# DancingLightBluetoothSpeakerTE_MP_Projec.net
KiCad netlist of a schematic drawn in EAGLE
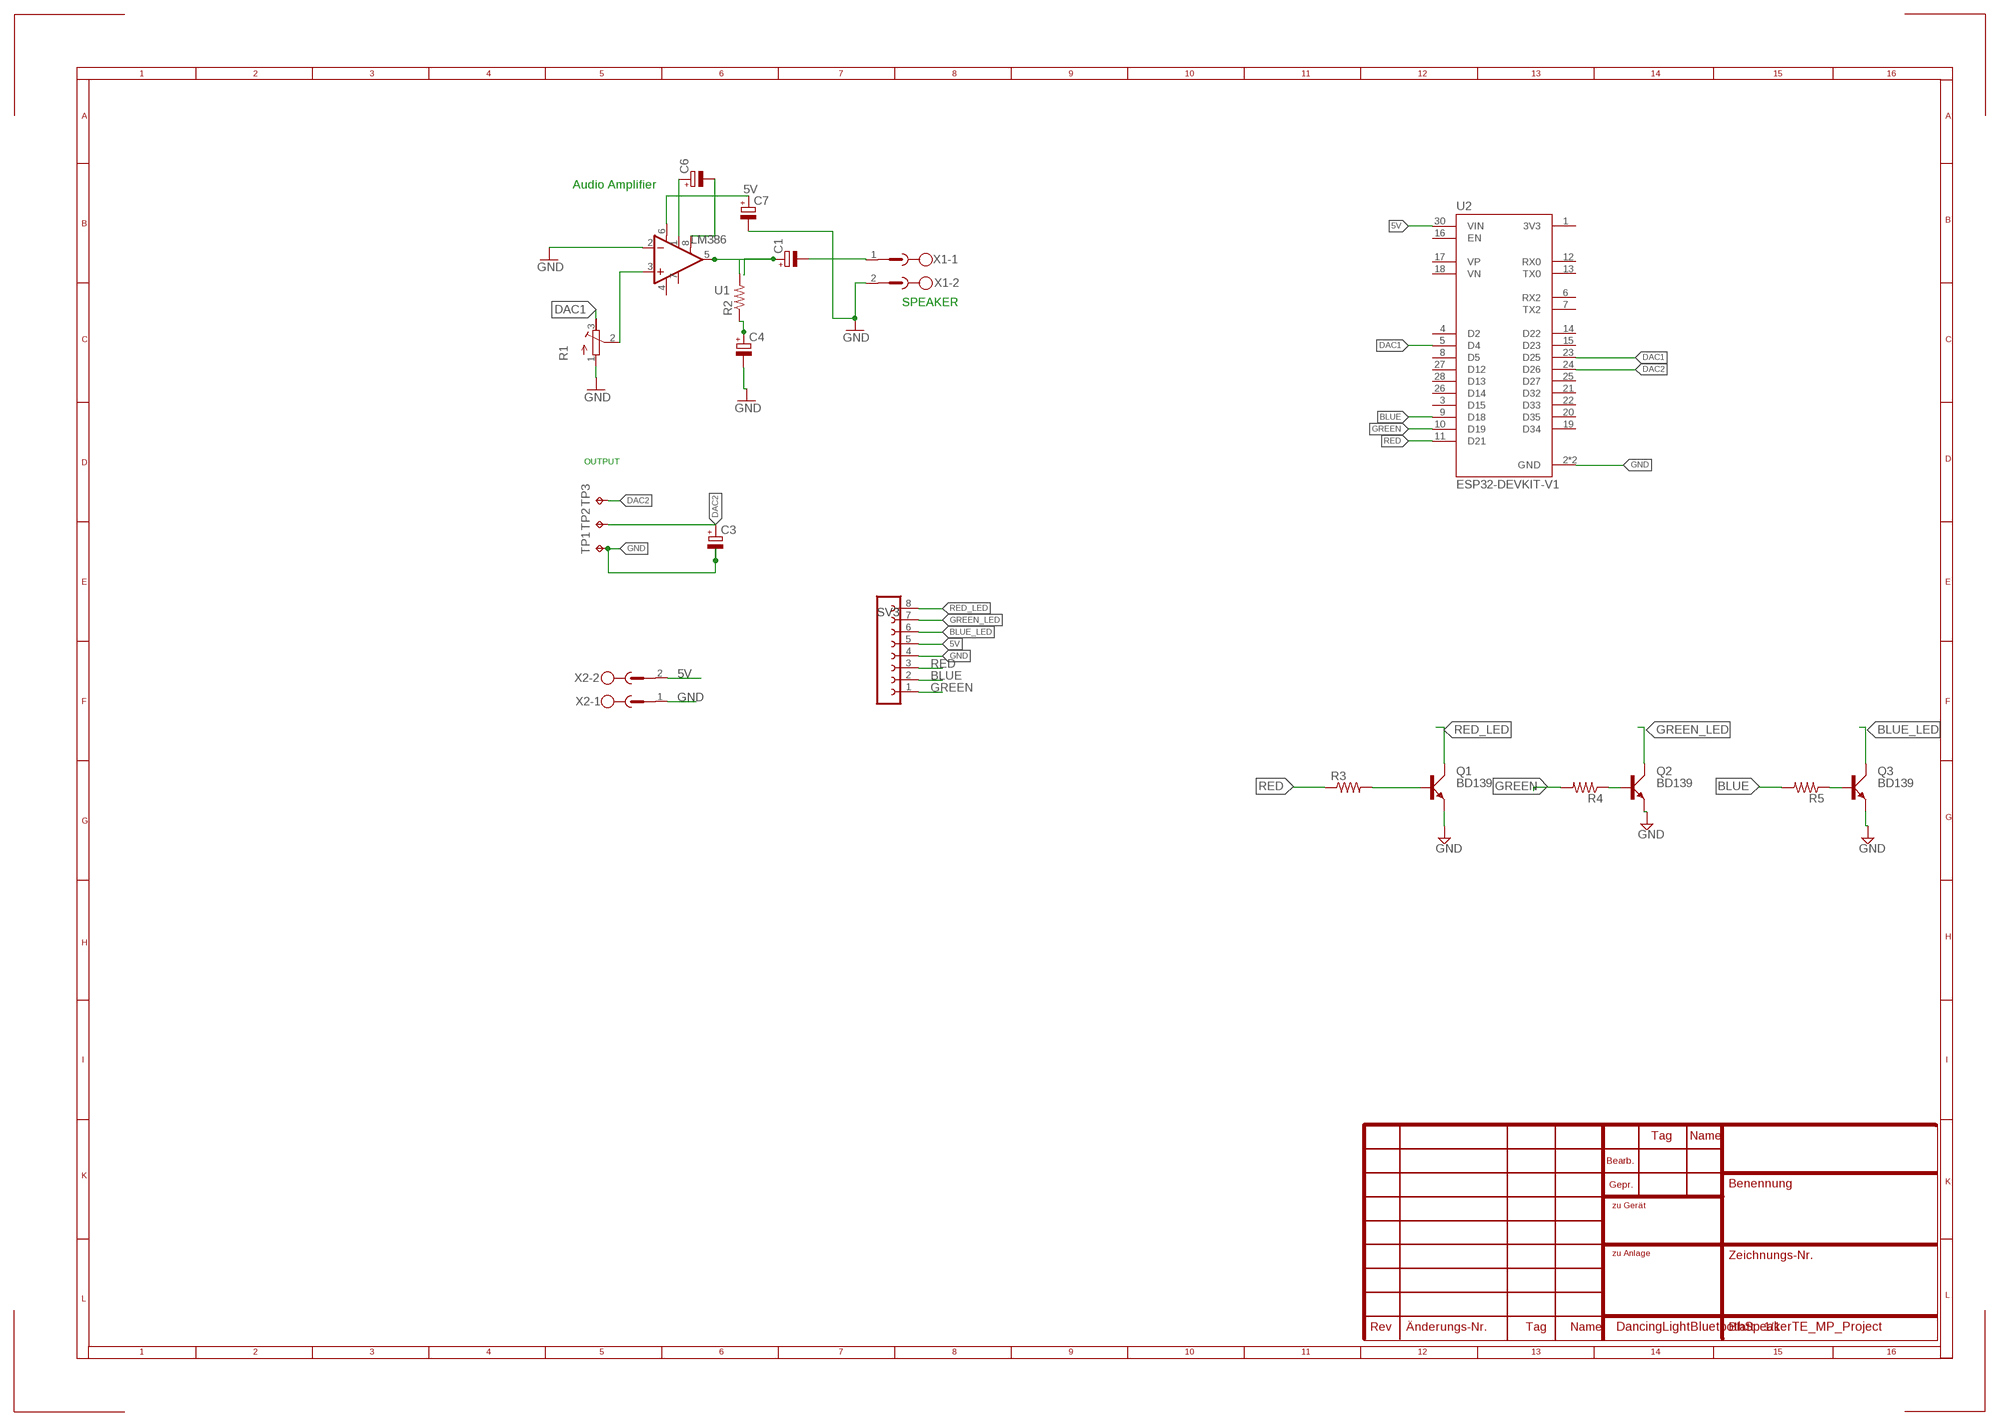
[diagram p0: schematic, sheet 1]

(export (version "E")
  (design (tool "Eeschema 10.0.6"))
  (components
    (comp (ref "C1")
      (value "CPOL-EUE2-5")
      (footprint "eagle-import:E2-5")
      (libsource (lib "eagle-import") (part "CPOL-EUE2-5"))
    )
    (comp (ref "C3")
      (value "CPOL-EUE2-5")
      (footprint "eagle-import:E2-5")
      (libsource (lib "eagle-import") (part "CPOL-EUE2-5"))
    )
    (comp (ref "C4")
      (value "CPOL-EUE2-5")
      (footprint "eagle-import:E2-5")
      (libsource (lib "eagle-import") (part "CPOL-EUE2-5"))
    )
    (comp (ref "C6")
      (value "CPOL-EUE2-5")
      (footprint "eagle-import:E2-5")
      (libsource (lib "eagle-import") (part "CPOL-EUE2-5"))
    )
    (comp (ref "C7")
      (value "CPOL-EUE2-5")
      (footprint "eagle-import:E2-5")
      (libsource (lib "eagle-import") (part "CPOL-EUE2-5"))
    )
    (comp (ref "Q1")
      (value "BD139")
      (footprint "eagle-import:TO126AV")
      (libsource (lib "eagle-import") (part "BD139"))
    )
    (comp (ref "Q2")
      (value "BD139")
      (footprint "eagle-import:TO126AV")
      (libsource (lib "eagle-import") (part "BD139"))
    )
    (comp (ref "Q3")
      (value "BD139")
      (footprint "eagle-import:TO126AV")
      (libsource (lib "eagle-import") (part "BD139"))
    )
    (comp (ref "R1")
      (value "R-TRIMM3339P")
      (footprint "eagle-import:RTRIM3339P")
      (libsource (lib "eagle-import") (part "R-TRIMM3339P"))
    )
    (comp (ref "R2")
      (value "R-US_0207/10")
      (footprint "eagle-import:0207_10")
      (libsource (lib "eagle-import") (part "R-US_0207/10"))
    )
    (comp (ref "R3")
      (value "R-US_0207/10")
      (footprint "eagle-import:0207_10")
      (libsource (lib "eagle-import") (part "R-US_0207/10"))
    )
    (comp (ref "R4")
      (value "R-US_0207/10")
      (footprint "eagle-import:0207_10")
      (libsource (lib "eagle-import") (part "R-US_0207/10"))
    )
    (comp (ref "R5")
      (value "R-US_0207/10")
      (footprint "eagle-import:0207_10")
      (libsource (lib "eagle-import") (part "R-US_0207/10"))
    )
    (comp (ref "SV3")
      (value "FE08-1")
      (footprint "eagle-import:FE08")
      (libsource (lib "eagle-import") (part "FE08-1"))
    )
    (comp (ref "TP1")
      (value "TPTP10SQ")
      (footprint "eagle-import:TP10SQ")
      (libsource (lib "eagle-import") (part "TPTP10SQ"))
    )
    (comp (ref "TP2")
      (value "TPTP10SQ")
      (footprint "eagle-import:TP10SQ")
      (libsource (lib "eagle-import") (part "TPTP10SQ"))
    )
    (comp (ref "TP3")
      (value "TPTP10SQ")
      (footprint "eagle-import:TP10SQ")
      (libsource (lib "eagle-import") (part "TPTP10SQ"))
    )
    (comp (ref "U1")
      (value "LM386")
      (footprint "eagle-import:DIP08")
      (fields (field (name "MF") "Texas Instruments"))
      (libsource (lib "eagle-import") (part "LM386"))
    )
    (comp (ref "U2")
      (value "ESP32-DEVKIT-V1")
      (footprint "eagle-import:MODULE_ESP32_DEVKIT_V1")
      (fields (field (name "MF") "Do it"))
      (libsource (lib "eagle-import") (part "ESP32-DEVKIT-V1"))
    )
    (comp (ref "X1")
      (value "MSTBV2")
      (footprint "eagle-import:MSTBV2")
      (libsource (lib "eagle-import") (part "MSTBV2"))
    )
    (comp (ref "X2")
      (value "MSTBV2")
      (footprint "eagle-import:MSTBV2")
      (libsource (lib "eagle-import") (part "MSTBV2"))
    )
  )
  (nets
    (net (code "1") (name "/V-") (class "Default")
      (node (ref "U1") (pin "4") (pinfunction "V-_4") (pintype "power_in"))
    )
    (net (code "2") (name "5V") (class "Default")
      (node (ref "C7") (pin "+") (pinfunction "+_+") (pintype "passive"))
      (node (ref "SV3") (pin "5") (pinfunction "5_5") (pintype "passive"))
      (node (ref "U1") (pin "6") (pinfunction "V+_6") (pintype "power_in"))
      (node (ref "U2") (pin "30") (pinfunction "VIN_30") (pintype "input"))
      (node (ref "X2") (pin "2") (pinfunction "SK_2") (pintype "passive"))
    )
    (net (code "3") (name "BLUE") (class "Default")
      (node (ref "R5") (pin "2") (pinfunction "2_2") (pintype "passive"))
      (node (ref "SV3") (pin "2") (pinfunction "2_2") (pintype "passive"))
      (node (ref "U2") (pin "9") (pinfunction "D18_9") (pintype "bidirectional"))
    )
    (net (code "4") (name "BLUE_LED") (class "Default")
      (node (ref "Q3") (pin "C") (pinfunction "C_C") (pintype "passive"))
      (node (ref "SV3") (pin "6") (pinfunction "6_6") (pintype "passive"))
    )
    (net (code "5") (name "DAC1") (class "Default")
      (node (ref "R1") (pin "3") (pinfunction "E_3") (pintype "passive"))
      (node (ref "U2") (pin "23") (pinfunction "D25_23") (pintype "bidirectional"))
      (node (ref "U2") (pin "5") (pinfunction "D4_5") (pintype "bidirectional"))
    )
    (net (code "6") (name "DAC2") (class "Default")
      (node (ref "C3") (pin "+") (pinfunction "+_+") (pintype "passive"))
      (node (ref "TP2") (pin "TP") (pinfunction "TP_TP") (pintype "input"))
      (node (ref "TP3") (pin "TP") (pinfunction "TP_TP") (pintype "input"))
      (node (ref "U2") (pin "24") (pinfunction "D26_24") (pintype "bidirectional"))
    )
    (net (code "7") (name "GND") (class "Default")
      (node (ref "C3") (pin "-") (pinfunction "-_-") (pintype "passive"))
      (node (ref "C4") (pin "-") (pinfunction "-_-") (pintype "passive"))
      (node (ref "C7") (pin "-") (pinfunction "-_-") (pintype "passive"))
      (node (ref "Q1") (pin "E") (pinfunction "E_E") (pintype "passive"))
      (node (ref "Q2") (pin "E") (pinfunction "E_E") (pintype "passive"))
      (node (ref "Q3") (pin "E") (pinfunction "E_E") (pintype "passive"))
      (node (ref "R1") (pin "1") (pinfunction "A_1") (pintype "passive"))
      (node (ref "SV3") (pin "4") (pinfunction "4_4") (pintype "passive"))
      (node (ref "TP1") (pin "TP") (pinfunction "TP_TP") (pintype "input"))
      (node (ref "U1") (pin "2") (pinfunction "-IN_2") (pintype "input"))
      (node (ref "U2") (pin "2") (pinfunction "GND_2") (pintype "power_in"))
      (node (ref "U2") (pin "29") (pinfunction "GND_29") (pintype "power_in"))
      (node (ref "X1") (pin "2") (pinfunction "SK_2") (pintype "passive"))
      (node (ref "X2") (pin "1") (pinfunction "SK_1") (pintype "passive"))
    )
    (net (code "8") (name "GREEN") (class "Default")
      (node (ref "R4") (pin "2") (pinfunction "2_2") (pintype "passive"))
      (node (ref "SV3") (pin "1") (pinfunction "1_1") (pintype "passive"))
      (node (ref "U2") (pin "10") (pinfunction "D19_10") (pintype "bidirectional"))
    )
    (net (code "9") (name "GREEN_LED") (class "Default")
      (node (ref "Q2") (pin "C") (pinfunction "C_C") (pintype "passive"))
      (node (ref "SV3") (pin "7") (pinfunction "7_7") (pintype "passive"))
    )
    (net (code "10") (name "Net-(C4-Pad+)") (class "Default")
      (node (ref "C4") (pin "+") (pinfunction "+_+") (pintype "passive"))
      (node (ref "R2") (pin "1") (pinfunction "1_1") (pintype "passive"))
    )
    (net (code "11") (name "Net-(C6-Pad+)") (class "Default")
      (node (ref "C6") (pin "+") (pinfunction "+_+") (pintype "passive"))
      (node (ref "U1") (pin "1") (pinfunction "GAIN_1") (pintype "bidirectional"))
    )
    (net (code "12") (name "Net-(C6-Pad-)") (class "Default")
      (node (ref "C6") (pin "-") (pinfunction "-_-") (pintype "passive"))
      (node (ref "U1") (pin "8") (pinfunction "GAIN_8") (pintype "bidirectional"))
    )
    (net (code "13") (name "Net-(Q1-PadB)") (class "Default")
      (node (ref "Q1") (pin "B") (pinfunction "B_B") (pintype "passive"))
      (node (ref "R3") (pin "2") (pinfunction "2_2") (pintype "passive"))
    )
    (net (code "14") (name "Net-(Q2-PadB)") (class "Default")
      (node (ref "Q2") (pin "B") (pinfunction "B_B") (pintype "passive"))
      (node (ref "R4") (pin "1") (pinfunction "1_1") (pintype "passive"))
    )
    (net (code "15") (name "Net-(Q3-PadB)") (class "Default")
      (node (ref "Q3") (pin "B") (pinfunction "B_B") (pintype "passive"))
      (node (ref "R5") (pin "1") (pinfunction "1_1") (pintype "passive"))
    )
    (net (code "16") (name "Net-(R1-S)") (class "Default")
      (node (ref "R1") (pin "2") (pinfunction "S_2") (pintype "passive"))
      (node (ref "U1") (pin "3") (pinfunction "+IN_3") (pintype "input"))
    )
    (net (code "17") (name "Net-(U1-OUT)") (class "Default")
      (node (ref "C1") (pin "+") (pinfunction "+_+") (pintype "passive"))
      (node (ref "R2") (pin "2") (pinfunction "2_2") (pintype "passive"))
      (node (ref "U1") (pin "5") (pinfunction "OUT_5") (pintype "output"))
    )
    (net (code "18") (name "Net-(X1A-SK)") (class "Default")
      (node (ref "C1") (pin "-") (pinfunction "-_-") (pintype "passive"))
      (node (ref "X1") (pin "1") (pinfunction "SK_1") (pintype "passive"))
    )
    (net (code "19") (name "RED") (class "Default")
      (node (ref "R3") (pin "1") (pinfunction "1_1") (pintype "passive"))
      (node (ref "SV3") (pin "3") (pinfunction "3_3") (pintype "passive"))
      (node (ref "U2") (pin "11") (pinfunction "D21_11") (pintype "bidirectional"))
    )
    (net (code "20") (name "RED_LED") (class "Default")
      (node (ref "Q1") (pin "C") (pinfunction "C_C") (pintype "passive"))
      (node (ref "SV3") (pin "8") (pinfunction "8_8") (pintype "passive"))
    )
    (net (code "21") (name "unconnected-(U1-BP-Pad7)") (class "Default")
      (node (ref "U1") (pin "7") (pinfunction "BP_7") (pintype "bidirectional"))
    )
    (net (code "22") (name "unconnected-(U2-3V3-Pad1)") (class "Default")
      (node (ref "U2") (pin "1") (pinfunction "3V3_1") (pintype "output"))
    )
    (net (code "23") (name "unconnected-(U2-D2-Pad4)") (class "Default")
      (node (ref "U2") (pin "4") (pinfunction "D2_4") (pintype "bidirectional"))
    )
    (net (code "24") (name "unconnected-(U2-D5-Pad8)") (class "Default")
      (node (ref "U2") (pin "8") (pinfunction "D5_8") (pintype "bidirectional"))
    )
    (net (code "25") (name "unconnected-(U2-D12-Pad27)") (class "Default")
      (node (ref "U2") (pin "27") (pinfunction "D12_27") (pintype "bidirectional"))
    )
    (net (code "26") (name "unconnected-(U2-D13-Pad28)") (class "Default")
      (node (ref "U2") (pin "28") (pinfunction "D13_28") (pintype "bidirectional"))
    )
    (net (code "27") (name "unconnected-(U2-D14-Pad26)") (class "Default")
      (node (ref "U2") (pin "26") (pinfunction "D14_26") (pintype "bidirectional"))
    )
    (net (code "28") (name "unconnected-(U2-D15-Pad3)") (class "Default")
      (node (ref "U2") (pin "3") (pinfunction "D15_3") (pintype "bidirectional"))
    )
    (net (code "29") (name "unconnected-(U2-D22-Pad14)") (class "Default")
      (node (ref "U2") (pin "14") (pinfunction "D22_14") (pintype "bidirectional"))
    )
    (net (code "30") (name "unconnected-(U2-D23-Pad15)") (class "Default")
      (node (ref "U2") (pin "15") (pinfunction "D23_15") (pintype "bidirectional"))
    )
    (net (code "31") (name "unconnected-(U2-D27-Pad25)") (class "Default")
      (node (ref "U2") (pin "25") (pinfunction "D27_25") (pintype "bidirectional"))
    )
    (net (code "32") (name "unconnected-(U2-D32-Pad21)") (class "Default")
      (node (ref "U2") (pin "21") (pinfunction "D32_21") (pintype "bidirectional"))
    )
    (net (code "33") (name "unconnected-(U2-D33-Pad22)") (class "Default")
      (node (ref "U2") (pin "22") (pinfunction "D33_22") (pintype "bidirectional"))
    )
    (net (code "34") (name "unconnected-(U2-D34-Pad19)") (class "Default")
      (node (ref "U2") (pin "19") (pinfunction "D34_19") (pintype "bidirectional"))
    )
    (net (code "35") (name "unconnected-(U2-D35-Pad20)") (class "Default")
      (node (ref "U2") (pin "20") (pinfunction "D35_20") (pintype "bidirectional"))
    )
    (net (code "36") (name "unconnected-(U2-EN-Pad16)") (class "Default")
      (node (ref "U2") (pin "16") (pinfunction "EN_16") (pintype "input"))
    )
    (net (code "37") (name "unconnected-(U2-RX0-Pad12)") (class "Default")
      (node (ref "U2") (pin "12") (pinfunction "RX0_12") (pintype "input"))
    )
    (net (code "38") (name "unconnected-(U2-RX2-Pad6)") (class "Default")
      (node (ref "U2") (pin "6") (pinfunction "RX2_6") (pintype "input"))
    )
    (net (code "39") (name "unconnected-(U2-TX0-Pad13)") (class "Default")
      (node (ref "U2") (pin "13") (pinfunction "TX0_13") (pintype "output"))
    )
    (net (code "40") (name "unconnected-(U2-TX2-Pad7)") (class "Default")
      (node (ref "U2") (pin "7") (pinfunction "TX2_7") (pintype "output"))
    )
    (net (code "41") (name "unconnected-(U2-VN-Pad18)") (class "Default")
      (node (ref "U2") (pin "18") (pinfunction "VN_18") (pintype "bidirectional"))
    )
    (net (code "42") (name "unconnected-(U2-VP-Pad17)") (class "Default")
      (node (ref "U2") (pin "17") (pinfunction "VP_17") (pintype "bidirectional"))
    )
  )
)
